# K7410tFFG900Power.net
KiCad netlist of a schematic drawn in Altium Designer
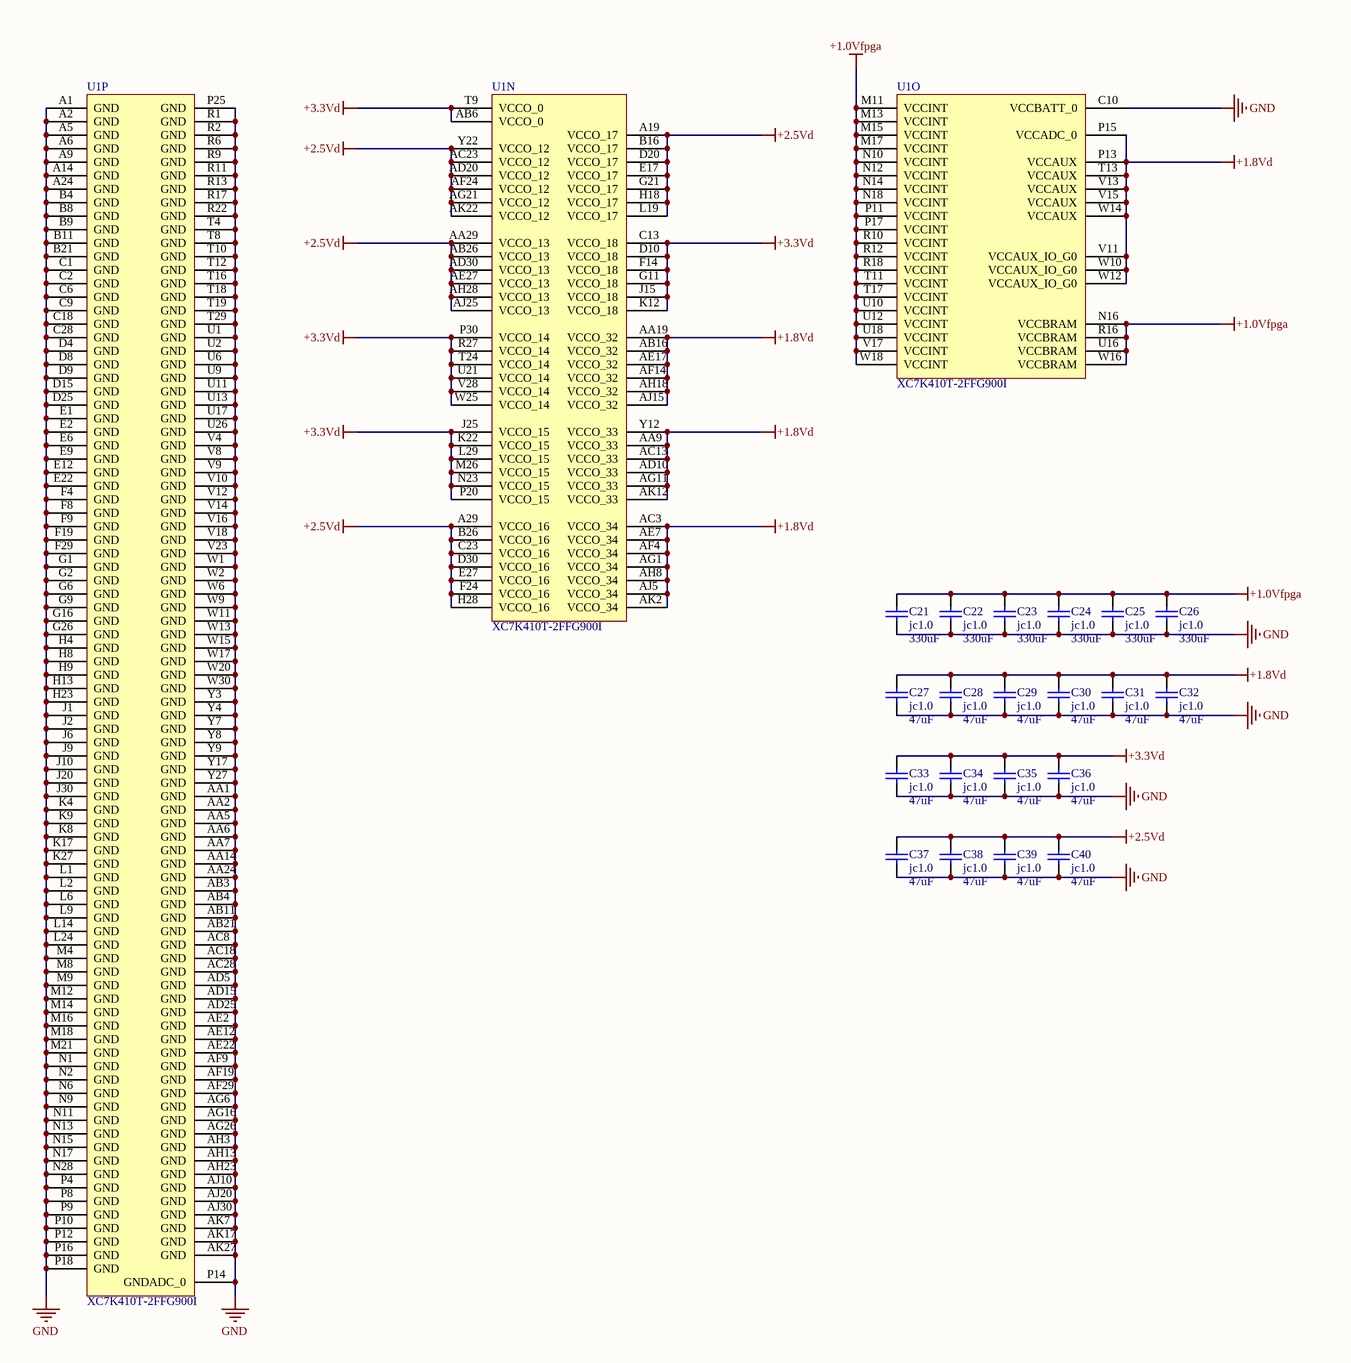
[diagram p0: K7410tFFG900Power.SchDoc]

(export (version "E")
  (design (tool "Eeschema 10.0.6"))
  (components
    (comp (ref "C21")
      (value "jc1.0")
      (footprint "2220")
      (description "Capacitor")
      (fields (field (name "ALTIUM_VALUE") "330uF") (field (name "PUBLISHER") "Altium Limited"))
      (libsource (lib "LIB01DXP2006SchLib") (part "Cap"))
    )
    (comp (ref "C22")
      (value "jc1.0")
      (footprint "2220")
      (description "Capacitor")
      (fields (field (name "ALTIUM_VALUE") "330uF") (field (name "PUBLISHER") "Altium Limited"))
      (libsource (lib "LIB01DXP2006SchLib") (part "Cap"))
    )
    (comp (ref "C23")
      (value "jc1.0")
      (footprint "2220")
      (description "Capacitor")
      (fields (field (name "ALTIUM_VALUE") "330uF") (field (name "PUBLISHER") "Altium Limited"))
      (libsource (lib "LIB01DXP2006SchLib") (part "Cap"))
    )
    (comp (ref "C24")
      (value "jc1.0")
      (footprint "2220")
      (description "Capacitor")
      (fields (field (name "ALTIUM_VALUE") "330uF") (field (name "PUBLISHER") "Altium Limited"))
      (libsource (lib "LIB01DXP2006SchLib") (part "Cap"))
    )
    (comp (ref "C25")
      (value "jc1.0")
      (footprint "2220")
      (description "Capacitor")
      (fields (field (name "ALTIUM_VALUE") "330uF") (field (name "PUBLISHER") "Altium Limited"))
      (libsource (lib "LIB01DXP2006SchLib") (part "Cap"))
    )
    (comp (ref "C26")
      (value "jc1.0")
      (footprint "2220")
      (description "Capacitor")
      (fields (field (name "ALTIUM_VALUE") "330uF") (field (name "PUBLISHER") "Altium Limited"))
      (libsource (lib "LIB01DXP2006SchLib") (part "Cap"))
    )
    (comp (ref "C27")
      (value "jc1.0")
      (footprint "1210")
      (description "Capacitor")
      (fields (field (name "ALTIUM_VALUE") "47uF") (field (name "PUBLISHER") "Altium Limited"))
      (libsource (lib "LIB01DXP2006SchLib") (part "Cap"))
    )
    (comp (ref "C28")
      (value "jc1.0")
      (footprint "1210")
      (description "Capacitor")
      (fields (field (name "ALTIUM_VALUE") "47uF") (field (name "PUBLISHER") "Altium Limited"))
      (libsource (lib "LIB01DXP2006SchLib") (part "Cap"))
    )
    (comp (ref "C29")
      (value "jc1.0")
      (footprint "1210")
      (description "Capacitor")
      (fields (field (name "ALTIUM_VALUE") "47uF") (field (name "PUBLISHER") "Altium Limited"))
      (libsource (lib "LIB01DXP2006SchLib") (part "Cap"))
    )
    (comp (ref "C30")
      (value "jc1.0")
      (footprint "1210")
      (description "Capacitor")
      (fields (field (name "ALTIUM_VALUE") "47uF") (field (name "PUBLISHER") "Altium Limited"))
      (libsource (lib "LIB01DXP2006SchLib") (part "Cap"))
    )
    (comp (ref "C31")
      (value "jc1.0")
      (footprint "1210")
      (description "Capacitor")
      (fields (field (name "ALTIUM_VALUE") "47uF") (field (name "PUBLISHER") "Altium Limited"))
      (libsource (lib "LIB01DXP2006SchLib") (part "Cap"))
    )
    (comp (ref "C32")
      (value "jc1.0")
      (footprint "1210")
      (description "Capacitor")
      (fields (field (name "ALTIUM_VALUE") "47uF") (field (name "PUBLISHER") "Altium Limited"))
      (libsource (lib "LIB01DXP2006SchLib") (part "Cap"))
    )
    (comp (ref "C33")
      (value "jc1.0")
      (footprint "1210")
      (description "Capacitor")
      (fields (field (name "ALTIUM_VALUE") "47uF") (field (name "PUBLISHER") "Altium Limited"))
      (libsource (lib "LIB01DXP2006SchLib") (part "Cap"))
    )
    (comp (ref "C34")
      (value "jc1.0")
      (footprint "1210")
      (description "Capacitor")
      (fields (field (name "ALTIUM_VALUE") "47uF") (field (name "PUBLISHER") "Altium Limited"))
      (libsource (lib "LIB01DXP2006SchLib") (part "Cap"))
    )
    (comp (ref "C35")
      (value "jc1.0")
      (footprint "1210")
      (description "Capacitor")
      (fields (field (name "ALTIUM_VALUE") "47uF") (field (name "PUBLISHER") "Altium Limited"))
      (libsource (lib "LIB01DXP2006SchLib") (part "Cap"))
    )
    (comp (ref "C36")
      (value "jc1.0")
      (footprint "1210")
      (description "Capacitor")
      (fields (field (name "ALTIUM_VALUE") "47uF") (field (name "PUBLISHER") "Altium Limited"))
      (libsource (lib "LIB01DXP2006SchLib") (part "Cap"))
    )
    (comp (ref "C37")
      (value "jc1.0")
      (footprint "1210")
      (description "Capacitor")
      (fields (field (name "ALTIUM_VALUE") "47uF") (field (name "PUBLISHER") "Altium Limited"))
      (libsource (lib "LIB01DXP2006SchLib") (part "Cap"))
    )
    (comp (ref "C38")
      (value "jc1.0")
      (footprint "1210")
      (description "Capacitor")
      (fields (field (name "ALTIUM_VALUE") "47uF") (field (name "PUBLISHER") "Altium Limited"))
      (libsource (lib "LIB01DXP2006SchLib") (part "Cap"))
    )
    (comp (ref "C39")
      (value "jc1.0")
      (footprint "1210")
      (description "Capacitor")
      (fields (field (name "ALTIUM_VALUE") "47uF") (field (name "PUBLISHER") "Altium Limited"))
      (libsource (lib "LIB01DXP2006SchLib") (part "Cap"))
    )
    (comp (ref "C40")
      (value "jc1.0")
      (footprint "1210")
      (description "Capacitor")
      (fields (field (name "ALTIUM_VALUE") "47uF") (field (name "PUBLISHER") "Altium Limited"))
      (libsource (lib "LIB01DXP2006SchLib") (part "Cap"))
    )
    (comp (ref "U1")
      (value "XC7K410T-2FFG900I")
      (footprint "FFG900")
      (description "Kintex-7 FPGA, 500 User I/Os, 16 GTX, 900-Ball BGA, Speed Grade 2, Industrial Grade, Pb-Free")
      (fields (field (name "GENERIC PART NUMBER") "XC7K410T") (field (name "MANUFACTURER") "Xilinx"))
      (libsource (lib "Xilinx Kintex-7") (part "XC7K410T-2FFG900I"))
    )
  )
  (nets
    (net (code "1") (name "+1.0Vfpga") (class "Default")
      (node (ref "C21") (pin "2") (pinfunction "2_2") (pintype "passive"))
      (node (ref "C22") (pin "2") (pinfunction "2_2") (pintype "passive"))
      (node (ref "C23") (pin "2") (pinfunction "2_2") (pintype "passive"))
      (node (ref "C24") (pin "2") (pinfunction "2_2") (pintype "passive"))
      (node (ref "C25") (pin "2") (pinfunction "2_2") (pintype "passive"))
      (node (ref "C26") (pin "2") (pinfunction "2_2") (pintype "passive"))
      (node (ref "U1") (pin "M11") (pinfunction "VCCINT_M11") (pintype "power_in"))
      (node (ref "U1") (pin "M13") (pinfunction "VCCINT_M13") (pintype "power_in"))
      (node (ref "U1") (pin "M15") (pinfunction "VCCINT_M15") (pintype "power_in"))
      (node (ref "U1") (pin "M17") (pinfunction "VCCINT_M17") (pintype "power_in"))
      (node (ref "U1") (pin "N10") (pinfunction "VCCINT_N10") (pintype "power_in"))
      (node (ref "U1") (pin "N12") (pinfunction "VCCINT_N12") (pintype "power_in"))
      (node (ref "U1") (pin "N14") (pinfunction "VCCINT_N14") (pintype "power_in"))
      (node (ref "U1") (pin "N16") (pinfunction "VCCBRAM_N16") (pintype "power_in"))
      (node (ref "U1") (pin "N18") (pinfunction "VCCINT_N18") (pintype "power_in"))
      (node (ref "U1") (pin "P11") (pinfunction "VCCINT_P11") (pintype "power_in"))
      (node (ref "U1") (pin "P17") (pinfunction "VCCINT_P17") (pintype "power_in"))
      (node (ref "U1") (pin "R10") (pinfunction "VCCINT_R10") (pintype "power_in"))
      (node (ref "U1") (pin "R12") (pinfunction "VCCINT_R12") (pintype "power_in"))
      (node (ref "U1") (pin "R16") (pinfunction "VCCBRAM_R16") (pintype "power_in"))
      (node (ref "U1") (pin "R18") (pinfunction "VCCINT_R18") (pintype "power_in"))
      (node (ref "U1") (pin "T11") (pinfunction "VCCINT_T11") (pintype "power_in"))
      (node (ref "U1") (pin "T17") (pinfunction "VCCINT_T17") (pintype "power_in"))
      (node (ref "U1") (pin "U10") (pinfunction "VCCINT_U10") (pintype "power_in"))
      (node (ref "U1") (pin "U12") (pinfunction "VCCINT_U12") (pintype "power_in"))
      (node (ref "U1") (pin "U16") (pinfunction "VCCBRAM_U16") (pintype "power_in"))
      (node (ref "U1") (pin "U18") (pinfunction "VCCINT_U18") (pintype "power_in"))
      (node (ref "U1") (pin "V17") (pinfunction "VCCINT_V17") (pintype "power_in"))
      (node (ref "U1") (pin "W16") (pinfunction "VCCBRAM_W16") (pintype "power_in"))
      (node (ref "U1") (pin "W18") (pinfunction "VCCINT_W18") (pintype "power_in"))
    )
    (net (code "2") (name "+1.8Vd") (class "Default")
      (node (ref "C27") (pin "2") (pinfunction "2_2") (pintype "passive"))
      (node (ref "C28") (pin "2") (pinfunction "2_2") (pintype "passive"))
      (node (ref "C29") (pin "2") (pinfunction "2_2") (pintype "passive"))
      (node (ref "C30") (pin "2") (pinfunction "2_2") (pintype "passive"))
      (node (ref "C31") (pin "2") (pinfunction "2_2") (pintype "passive"))
      (node (ref "C32") (pin "2") (pinfunction "2_2") (pintype "passive"))
      (node (ref "U1") (pin "AA19") (pinfunction "VCCO_32_AA19") (pintype "power_in"))
      (node (ref "U1") (pin "AA9") (pinfunction "VCCO_33_AA9") (pintype "power_in"))
      (node (ref "U1") (pin "AB16") (pinfunction "VCCO_32_AB16") (pintype "power_in"))
      (node (ref "U1") (pin "AC13") (pinfunction "VCCO_33_AC13") (pintype "power_in"))
      (node (ref "U1") (pin "AC3") (pinfunction "VCCO_34_AC3") (pintype "power_in"))
      (node (ref "U1") (pin "AD10") (pinfunction "VCCO_33_AD10") (pintype "power_in"))
      (node (ref "U1") (pin "AE17") (pinfunction "VCCO_32_AE17") (pintype "power_in"))
      (node (ref "U1") (pin "AE7") (pinfunction "VCCO_34_AE7") (pintype "power_in"))
      (node (ref "U1") (pin "AF14") (pinfunction "VCCO_32_AF14") (pintype "power_in"))
      (node (ref "U1") (pin "AF4") (pinfunction "VCCO_34_AF4") (pintype "power_in"))
      (node (ref "U1") (pin "AG1") (pinfunction "VCCO_34_AG1") (pintype "power_in"))
      (node (ref "U1") (pin "AG11") (pinfunction "VCCO_33_AG11") (pintype "power_in"))
      (node (ref "U1") (pin "AH18") (pinfunction "VCCO_32_AH18") (pintype "power_in"))
      (node (ref "U1") (pin "AH8") (pinfunction "VCCO_34_AH8") (pintype "power_in"))
      (node (ref "U1") (pin "AJ15") (pinfunction "VCCO_32_AJ15") (pintype "power_in"))
      (node (ref "U1") (pin "AJ5") (pinfunction "VCCO_34_AJ5") (pintype "power_in"))
      (node (ref "U1") (pin "AK12") (pinfunction "VCCO_33_AK12") (pintype "power_in"))
      (node (ref "U1") (pin "AK2") (pinfunction "VCCO_34_AK2") (pintype "power_in"))
      (node (ref "U1") (pin "P13") (pinfunction "VCCAUX_P13") (pintype "power_in"))
      (node (ref "U1") (pin "P15") (pinfunction "VCCADC_0_P15") (pintype "power_in"))
      (node (ref "U1") (pin "T13") (pinfunction "VCCAUX_T13") (pintype "power_in"))
      (node (ref "U1") (pin "V11") (pinfunction "VCCAUX_IO_G0_V11") (pintype "power_in"))
      (node (ref "U1") (pin "V13") (pinfunction "VCCAUX_V13") (pintype "power_in"))
      (node (ref "U1") (pin "V15") (pinfunction "VCCAUX_V15") (pintype "power_in"))
      (node (ref "U1") (pin "W10") (pinfunction "VCCAUX_IO_G0_W10") (pintype "power_in"))
      (node (ref "U1") (pin "W12") (pinfunction "VCCAUX_IO_G0_W12") (pintype "power_in"))
      (node (ref "U1") (pin "W14") (pinfunction "VCCAUX_W14") (pintype "power_in"))
      (node (ref "U1") (pin "Y12") (pinfunction "VCCO_33_Y12") (pintype "power_in"))
    )
    (net (code "3") (name "+2.5Vd") (class "Default")
      (node (ref "C37") (pin "2") (pinfunction "2_2") (pintype "passive"))
      (node (ref "C38") (pin "2") (pinfunction "2_2") (pintype "passive"))
      (node (ref "C39") (pin "2") (pinfunction "2_2") (pintype "passive"))
      (node (ref "C40") (pin "2") (pinfunction "2_2") (pintype "passive"))
      (node (ref "U1") (pin "A19") (pinfunction "VCCO_17_A19") (pintype "power_in"))
      (node (ref "U1") (pin "A29") (pinfunction "VCCO_16_A29") (pintype "power_in"))
      (node (ref "U1") (pin "AA29") (pinfunction "VCCO_13_AA29") (pintype "power_in"))
      (node (ref "U1") (pin "AB26") (pinfunction "VCCO_13_AB26") (pintype "power_in"))
      (node (ref "U1") (pin "AC23") (pinfunction "VCCO_12_AC23") (pintype "power_in"))
      (node (ref "U1") (pin "AD20") (pinfunction "VCCO_12_AD20") (pintype "power_in"))
      (node (ref "U1") (pin "AD30") (pinfunction "VCCO_13_AD30") (pintype "power_in"))
      (node (ref "U1") (pin "AE27") (pinfunction "VCCO_13_AE27") (pintype "power_in"))
      (node (ref "U1") (pin "AF24") (pinfunction "VCCO_12_AF24") (pintype "power_in"))
      (node (ref "U1") (pin "AG21") (pinfunction "VCCO_12_AG21") (pintype "power_in"))
      (node (ref "U1") (pin "AH28") (pinfunction "VCCO_13_AH28") (pintype "power_in"))
      (node (ref "U1") (pin "AJ25") (pinfunction "VCCO_13_AJ25") (pintype "power_in"))
      (node (ref "U1") (pin "AK22") (pinfunction "VCCO_12_AK22") (pintype "power_in"))
      (node (ref "U1") (pin "B16") (pinfunction "VCCO_17_B16") (pintype "power_in"))
      (node (ref "U1") (pin "B26") (pinfunction "VCCO_16_B26") (pintype "power_in"))
      (node (ref "U1") (pin "C23") (pinfunction "VCCO_16_C23") (pintype "power_in"))
      (node (ref "U1") (pin "D20") (pinfunction "VCCO_17_D20") (pintype "power_in"))
      (node (ref "U1") (pin "D30") (pinfunction "VCCO_16_D30") (pintype "power_in"))
      (node (ref "U1") (pin "E17") (pinfunction "VCCO_17_E17") (pintype "power_in"))
      (node (ref "U1") (pin "E27") (pinfunction "VCCO_16_E27") (pintype "power_in"))
      (node (ref "U1") (pin "F24") (pinfunction "VCCO_16_F24") (pintype "power_in"))
      (node (ref "U1") (pin "G21") (pinfunction "VCCO_17_G21") (pintype "power_in"))
      (node (ref "U1") (pin "H18") (pinfunction "VCCO_17_H18") (pintype "power_in"))
      (node (ref "U1") (pin "H28") (pinfunction "VCCO_16_H28") (pintype "power_in"))
      (node (ref "U1") (pin "L19") (pinfunction "VCCO_17_L19") (pintype "power_in"))
      (node (ref "U1") (pin "Y22") (pinfunction "VCCO_12_Y22") (pintype "power_in"))
    )
    (net (code "4") (name "+3.3Vd") (class "Default")
      (node (ref "C33") (pin "2") (pinfunction "2_2") (pintype "passive"))
      (node (ref "C34") (pin "2") (pinfunction "2_2") (pintype "passive"))
      (node (ref "C35") (pin "2") (pinfunction "2_2") (pintype "passive"))
      (node (ref "C36") (pin "2") (pinfunction "2_2") (pintype "passive"))
      (node (ref "U1") (pin "AB6") (pinfunction "VCCO_0_AB6") (pintype "power_in"))
      (node (ref "U1") (pin "C13") (pinfunction "VCCO_18_C13") (pintype "power_in"))
      (node (ref "U1") (pin "D10") (pinfunction "VCCO_18_D10") (pintype "power_in"))
      (node (ref "U1") (pin "F14") (pinfunction "VCCO_18_F14") (pintype "power_in"))
      (node (ref "U1") (pin "G11") (pinfunction "VCCO_18_G11") (pintype "power_in"))
      (node (ref "U1") (pin "J15") (pinfunction "VCCO_18_J15") (pintype "power_in"))
      (node (ref "U1") (pin "J25") (pinfunction "VCCO_15_J25") (pintype "power_in"))
      (node (ref "U1") (pin "K12") (pinfunction "VCCO_18_K12") (pintype "power_in"))
      (node (ref "U1") (pin "K22") (pinfunction "VCCO_15_K22") (pintype "power_in"))
      (node (ref "U1") (pin "L29") (pinfunction "VCCO_15_L29") (pintype "power_in"))
      (node (ref "U1") (pin "M26") (pinfunction "VCCO_15_M26") (pintype "power_in"))
      (node (ref "U1") (pin "N23") (pinfunction "VCCO_15_N23") (pintype "power_in"))
      (node (ref "U1") (pin "P20") (pinfunction "VCCO_15_P20") (pintype "power_in"))
      (node (ref "U1") (pin "P30") (pinfunction "VCCO_14_P30") (pintype "power_in"))
      (node (ref "U1") (pin "R27") (pinfunction "VCCO_14_R27") (pintype "power_in"))
      (node (ref "U1") (pin "T24") (pinfunction "VCCO_14_T24") (pintype "power_in"))
      (node (ref "U1") (pin "T9") (pinfunction "VCCO_0_T9") (pintype "power_in"))
      (node (ref "U1") (pin "U21") (pinfunction "VCCO_14_U21") (pintype "power_in"))
      (node (ref "U1") (pin "V28") (pinfunction "VCCO_14_V28") (pintype "power_in"))
      (node (ref "U1") (pin "W25") (pinfunction "VCCO_14_W25") (pintype "power_in"))
    )
    (net (code "5") (name "GND") (class "Default")
      (node (ref "C21") (pin "1") (pinfunction "1_1") (pintype "passive"))
      (node (ref "C22") (pin "1") (pinfunction "1_1") (pintype "passive"))
      (node (ref "C23") (pin "1") (pinfunction "1_1") (pintype "passive"))
      (node (ref "C24") (pin "1") (pinfunction "1_1") (pintype "passive"))
      (node (ref "C25") (pin "1") (pinfunction "1_1") (pintype "passive"))
      (node (ref "C26") (pin "1") (pinfunction "1_1") (pintype "passive"))
      (node (ref "C27") (pin "1") (pinfunction "1_1") (pintype "passive"))
      (node (ref "C28") (pin "1") (pinfunction "1_1") (pintype "passive"))
      (node (ref "C29") (pin "1") (pinfunction "1_1") (pintype "passive"))
      (node (ref "C30") (pin "1") (pinfunction "1_1") (pintype "passive"))
      (node (ref "C31") (pin "1") (pinfunction "1_1") (pintype "passive"))
      (node (ref "C32") (pin "1") (pinfunction "1_1") (pintype "passive"))
      (node (ref "C33") (pin "1") (pinfunction "1_1") (pintype "passive"))
      (node (ref "C34") (pin "1") (pinfunction "1_1") (pintype "passive"))
      (node (ref "C35") (pin "1") (pinfunction "1_1") (pintype "passive"))
      (node (ref "C36") (pin "1") (pinfunction "1_1") (pintype "passive"))
      (node (ref "C37") (pin "1") (pinfunction "1_1") (pintype "passive"))
      (node (ref "C38") (pin "1") (pinfunction "1_1") (pintype "passive"))
      (node (ref "C39") (pin "1") (pinfunction "1_1") (pintype "passive"))
      (node (ref "C40") (pin "1") (pinfunction "1_1") (pintype "passive"))
      (node (ref "U1") (pin "A1") (pinfunction "GND_A1") (pintype "power_in"))
      (node (ref "U1") (pin "A14") (pinfunction "GND_A14") (pintype "power_in"))
      (node (ref "U1") (pin "A2") (pinfunction "GND_A2") (pintype "power_in"))
      (node (ref "U1") (pin "A24") (pinfunction "GND_A24") (pintype "power_in"))
      (node (ref "U1") (pin "A5") (pinfunction "GND_A5") (pintype "power_in"))
      (node (ref "U1") (pin "A6") (pinfunction "GND_A6") (pintype "power_in"))
      (node (ref "U1") (pin "A9") (pinfunction "GND_A9") (pintype "power_in"))
      (node (ref "U1") (pin "AA1") (pinfunction "GND_AA1") (pintype "power_in"))
      (node (ref "U1") (pin "AA14") (pinfunction "GND_AA14") (pintype "power_in"))
      (node (ref "U1") (pin "AA2") (pinfunction "GND_AA2") (pintype "power_in"))
      (node (ref "U1") (pin "AA24") (pinfunction "GND_AA24") (pintype "power_in"))
      (node (ref "U1") (pin "AA5") (pinfunction "GND_AA5") (pintype "power_in"))
      (node (ref "U1") (pin "AA6") (pinfunction "GND_AA6") (pintype "power_in"))
      (node (ref "U1") (pin "AA7") (pinfunction "GND_AA7") (pintype "power_in"))
      (node (ref "U1") (pin "AB11") (pinfunction "GND_AB11") (pintype "power_in"))
      (node (ref "U1") (pin "AB21") (pinfunction "GND_AB21") (pintype "power_in"))
      (node (ref "U1") (pin "AB3") (pinfunction "GND_AB3") (pintype "power_in"))
      (node (ref "U1") (pin "AB4") (pinfunction "GND_AB4") (pintype "power_in"))
      (node (ref "U1") (pin "AC18") (pinfunction "GND_AC18") (pintype "power_in"))
      (node (ref "U1") (pin "AC28") (pinfunction "GND_AC28") (pintype "power_in"))
      (node (ref "U1") (pin "AC8") (pinfunction "GND_AC8") (pintype "power_in"))
      (node (ref "U1") (pin "AD15") (pinfunction "GND_AD15") (pintype "power_in"))
      (node (ref "U1") (pin "AD25") (pinfunction "GND_AD25") (pintype "power_in"))
      (node (ref "U1") (pin "AD5") (pinfunction "GND_AD5") (pintype "power_in"))
      (node (ref "U1") (pin "AE12") (pinfunction "GND_AE12") (pintype "power_in"))
      (node (ref "U1") (pin "AE2") (pinfunction "GND_AE2") (pintype "power_in"))
      (node (ref "U1") (pin "AE22") (pinfunction "GND_AE22") (pintype "power_in"))
      (node (ref "U1") (pin "AF19") (pinfunction "GND_AF19") (pintype "power_in"))
      (node (ref "U1") (pin "AF29") (pinfunction "GND_AF29") (pintype "power_in"))
      (node (ref "U1") (pin "AF9") (pinfunction "GND_AF9") (pintype "power_in"))
      (node (ref "U1") (pin "AG16") (pinfunction "GND_AG16") (pintype "power_in"))
      (node (ref "U1") (pin "AG26") (pinfunction "GND_AG26") (pintype "power_in"))
      (node (ref "U1") (pin "AG6") (pinfunction "GND_AG6") (pintype "power_in"))
      (node (ref "U1") (pin "AH13") (pinfunction "GND_AH13") (pintype "power_in"))
      (node (ref "U1") (pin "AH23") (pinfunction "GND_AH23") (pintype "power_in"))
      (node (ref "U1") (pin "AH3") (pinfunction "GND_AH3") (pintype "power_in"))
      (node (ref "U1") (pin "AJ10") (pinfunction "GND_AJ10") (pintype "power_in"))
      (node (ref "U1") (pin "AJ20") (pinfunction "GND_AJ20") (pintype "power_in"))
      (node (ref "U1") (pin "AJ30") (pinfunction "GND_AJ30") (pintype "power_in"))
      (node (ref "U1") (pin "AK17") (pinfunction "GND_AK17") (pintype "power_in"))
      (node (ref "U1") (pin "AK27") (pinfunction "GND_AK27") (pintype "power_in"))
      (node (ref "U1") (pin "AK7") (pinfunction "GND_AK7") (pintype "power_in"))
      (node (ref "U1") (pin "B11") (pinfunction "GND_B11") (pintype "power_in"))
      (node (ref "U1") (pin "B21") (pinfunction "GND_B21") (pintype "power_in"))
      (node (ref "U1") (pin "B4") (pinfunction "GND_B4") (pintype "power_in"))
      (node (ref "U1") (pin "B8") (pinfunction "GND_B8") (pintype "power_in"))
      (node (ref "U1") (pin "B9") (pinfunction "GND_B9") (pintype "power_in"))
      (node (ref "U1") (pin "C1") (pinfunction "GND_C1") (pintype "power_in"))
      (node (ref "U1") (pin "C10") (pinfunction "VCCBATT_0_C10") (pintype "power_in"))
      (node (ref "U1") (pin "C18") (pinfunction "GND_C18") (pintype "power_in"))
      (node (ref "U1") (pin "C2") (pinfunction "GND_C2") (pintype "power_in"))
      (node (ref "U1") (pin "C28") (pinfunction "GND_C28") (pintype "power_in"))
      (node (ref "U1") (pin "C6") (pinfunction "GND_C6") (pintype "power_in"))
      (node (ref "U1") (pin "C9") (pinfunction "GND_C9") (pintype "power_in"))
      (node (ref "U1") (pin "D15") (pinfunction "GND_D15") (pintype "power_in"))
      (node (ref "U1") (pin "D25") (pinfunction "GND_D25") (pintype "power_in"))
      (node (ref "U1") (pin "D4") (pinfunction "GND_D4") (pintype "power_in"))
      (node (ref "U1") (pin "D8") (pinfunction "GND_D8") (pintype "power_in"))
      (node (ref "U1") (pin "D9") (pinfunction "GND_D9") (pintype "power_in"))
      (node (ref "U1") (pin "E1") (pinfunction "GND_E1") (pintype "power_in"))
      (node (ref "U1") (pin "E12") (pinfunction "GND_E12") (pintype "power_in"))
      (node (ref "U1") (pin "E2") (pinfunction "GND_E2") (pintype "power_in"))
      (node (ref "U1") (pin "E22") (pinfunction "GND_E22") (pintype "power_in"))
      (node (ref "U1") (pin "E6") (pinfunction "GND_E6") (pintype "power_in"))
      (node (ref "U1") (pin "E9") (pinfunction "GND_E9") (pintype "power_in"))
      (node (ref "U1") (pin "F19") (pinfunction "GND_F19") (pintype "power_in"))
      (node (ref "U1") (pin "F29") (pinfunction "GND_F29") (pintype "power_in"))
      (node (ref "U1") (pin "F4") (pinfunction "GND_F4") (pintype "power_in"))
      (node (ref "U1") (pin "F8") (pinfunction "GND_F8") (pintype "power_in"))
      (node (ref "U1") (pin "F9") (pinfunction "GND_F9") (pintype "power_in"))
      (node (ref "U1") (pin "G1") (pinfunction "GND_G1") (pintype "power_in"))
      (node (ref "U1") (pin "G16") (pinfunction "GND_G16") (pintype "power_in"))
      (node (ref "U1") (pin "G2") (pinfunction "GND_G2") (pintype "power_in"))
      (node (ref "U1") (pin "G26") (pinfunction "GND_G26") (pintype "power_in"))
      (node (ref "U1") (pin "G6") (pinfunction "GND_G6") (pintype "power_in"))
      (node (ref "U1") (pin "G9") (pinfunction "GND_G9") (pintype "power_in"))
      (node (ref "U1") (pin "H13") (pinfunction "GND_H13") (pintype "power_in"))
      (node (ref "U1") (pin "H23") (pinfunction "GND_H23") (pintype "power_in"))
      (node (ref "U1") (pin "H4") (pinfunction "GND_H4") (pintype "power_in"))
      (node (ref "U1") (pin "H8") (pinfunction "GND_H8") (pintype "power_in"))
      (node (ref "U1") (pin "H9") (pinfunction "GND_H9") (pintype "power_in"))
      (node (ref "U1") (pin "J1") (pinfunction "GND_J1") (pintype "power_in"))
      (node (ref "U1") (pin "J10") (pinfunction "GND_J10") (pintype "power_in"))
      (node (ref "U1") (pin "J2") (pinfunction "GND_J2") (pintype "power_in"))
      (node (ref "U1") (pin "J20") (pinfunction "GND_J20") (pintype "power_in"))
      (node (ref "U1") (pin "J30") (pinfunction "GND_J30") (pintype "power_in"))
      (node (ref "U1") (pin "J6") (pinfunction "GND_J6") (pintype "power_in"))
      (node (ref "U1") (pin "J9") (pinfunction "GND_J9") (pintype "power_in"))
      (node (ref "U1") (pin "K17") (pinfunction "GND_K17") (pintype "power_in"))
      (node (ref "U1") (pin "K27") (pinfunction "GND_K27") (pintype "power_in"))
      (node (ref "U1") (pin "K4") (pinfunction "GND_K4") (pintype "power_in"))
      (node (ref "U1") (pin "K8") (pinfunction "GND_K8") (pintype "power_in"))
      (node (ref "U1") (pin "K9") (pinfunction "GND_K9") (pintype "power_in"))
      (node (ref "U1") (pin "L1") (pinfunction "GND_L1") (pintype "power_in"))
      (node (ref "U1") (pin "L14") (pinfunction "GND_L14") (pintype "power_in"))
      (node (ref "U1") (pin "L2") (pinfunction "GND_L2") (pintype "power_in"))
      (node (ref "U1") (pin "L24") (pinfunction "GND_L24") (pintype "power_in"))
      (node (ref "U1") (pin "L6") (pinfunction "GND_L6") (pintype "power_in"))
      (node (ref "U1") (pin "L9") (pinfunction "GND_L9") (pintype "power_in"))
      (node (ref "U1") (pin "M12") (pinfunction "GND_M12") (pintype "power_in"))
      (node (ref "U1") (pin "M14") (pinfunction "GND_M14") (pintype "power_in"))
      (node (ref "U1") (pin "M16") (pinfunction "GND_M16") (pintype "power_in"))
      (node (ref "U1") (pin "M18") (pinfunction "GND_M18") (pintype "power_in"))
      (node (ref "U1") (pin "M21") (pinfunction "GND_M21") (pintype "power_in"))
      (node (ref "U1") (pin "M4") (pinfunction "GND_M4") (pintype "power_in"))
      (node (ref "U1") (pin "M8") (pinfunction "GND_M8") (pintype "power_in"))
      (node (ref "U1") (pin "M9") (pinfunction "GND_M9") (pintype "power_in"))
      (node (ref "U1") (pin "N1") (pinfunction "GND_N1") (pintype "power_in"))
      (node (ref "U1") (pin "N11") (pinfunction "GND_N11") (pintype "power_in"))
      (node (ref "U1") (pin "N13") (pinfunction "GND_N13") (pintype "power_in"))
      (node (ref "U1") (pin "N15") (pinfunction "GND_N15") (pintype "power_in"))
      (node (ref "U1") (pin "N17") (pinfunction "GND_N17") (pintype "power_in"))
      (node (ref "U1") (pin "N2") (pinfunction "GND_N2") (pintype "power_in"))
      (node (ref "U1") (pin "N28") (pinfunction "GND_N28") (pintype "power_in"))
      (node (ref "U1") (pin "N6") (pinfunction "GND_N6") (pintype "power_in"))
      (node (ref "U1") (pin "N9") (pinfunction "GND_N9") (pintype "power_in"))
      (node (ref "U1") (pin "P10") (pinfunction "GND_P10") (pintype "power_in"))
      (node (ref "U1") (pin "P12") (pinfunction "GND_P12") (pintype "power_in"))
      (node (ref "U1") (pin "P14") (pinfunction "GNDADC_0_P14") (pintype "power_in"))
      (node (ref "U1") (pin "P16") (pinfunction "GND_P16") (pintype "power_in"))
      (node (ref "U1") (pin "P18") (pinfunction "GND_P18") (pintype "power_in"))
      (node (ref "U1") (pin "P25") (pinfunction "GND_P25") (pintype "power_in"))
      (node (ref "U1") (pin "P4") (pinfunction "GND_P4") (pintype "power_in"))
      (node (ref "U1") (pin "P8") (pinfunction "GND_P8") (pintype "power_in"))
      (node (ref "U1") (pin "P9") (pinfunction "GND_P9") (pintype "power_in"))
      (node (ref "U1") (pin "R1") (pinfunction "GND_R1") (pintype "power_in"))
      (node (ref "U1") (pin "R11") (pinfunction "GND_R11") (pintype "power_in"))
      (node (ref "U1") (pin "R13") (pinfunction "GND_R13") (pintype "power_in"))
      (node (ref "U1") (pin "R17") (pinfunction "GND_R17") (pintype "power_in"))
      (node (ref "U1") (pin "R2") (pinfunction "GND_R2") (pintype "power_in"))
      (node (ref "U1") (pin "R22") (pinfunction "GND_R22") (pintype "power_in"))
      (node (ref "U1") (pin "R6") (pinfunction "GND_R6") (pintype "power_in"))
      (node (ref "U1") (pin "R9") (pinfunction "GND_R9") (pintype "power_in"))
      (node (ref "U1") (pin "T10") (pinfunction "GND_T10") (pintype "power_in"))
      (node (ref "U1") (pin "T12") (pinfunction "GND_T12") (pintype "power_in"))
      (node (ref "U1") (pin "T16") (pinfunction "GND_T16") (pintype "power_in"))
      (node (ref "U1") (pin "T18") (pinfunction "GND_T18") (pintype "power_in"))
      (node (ref "U1") (pin "T19") (pinfunction "GND_T19") (pintype "power_in"))
      (node (ref "U1") (pin "T29") (pinfunction "GND_T29") (pintype "power_in"))
      (node (ref "U1") (pin "T4") (pinfunction "GND_T4") (pintype "power_in"))
      (node (ref "U1") (pin "T8") (pinfunction "GND_T8") (pintype "power_in"))
      (node (ref "U1") (pin "U1") (pinfunction "GND_U1") (pintype "power_in"))
      (node (ref "U1") (pin "U11") (pinfunction "GND_U11") (pintype "power_in"))
      (node (ref "U1") (pin "U13") (pinfunction "GND_U13") (pintype "power_in"))
      (node (ref "U1") (pin "U17") (pinfunction "GND_U17") (pintype "power_in"))
      (node (ref "U1") (pin "U2") (pinfunction "GND_U2") (pintype "power_in"))
      (node (ref "U1") (pin "U26") (pinfunction "GND_U26") (pintype "power_in"))
      (node (ref "U1") (pin "U6") (pinfunction "GND_U6") (pintype "power_in"))
      (node (ref "U1") (pin "U9") (pinfunction "GND_U9") (pintype "power_in"))
      (node (ref "U1") (pin "V10") (pinfunction "GND_V10") (pintype "power_in"))
      (node (ref "U1") (pin "V12") (pinfunction "GND_V12") (pintype "power_in"))
      (node (ref "U1") (pin "V14") (pinfunction "GND_V14") (pintype "power_in"))
      (node (ref "U1") (pin "V16") (pinfunction "GND_V16") (pintype "power_in"))
      (node (ref "U1") (pin "V18") (pinfunction "GND_V18") (pintype "power_in"))
      (node (ref "U1") (pin "V23") (pinfunction "GND_V23") (pintype "power_in"))
      (node (ref "U1") (pin "V4") (pinfunction "GND_V4") (pintype "power_in"))
      (node (ref "U1") (pin "V8") (pinfunction "GND_V8") (pintype "power_in"))
      (node (ref "U1") (pin "V9") (pinfunction "GND_V9") (pintype "power_in"))
      (node (ref "U1") (pin "W1") (pinfunction "GND_W1") (pintype "power_in"))
      (node (ref "U1") (pin "W11") (pinfunction "GND_W11") (pintype "power_in"))
      (node (ref "U1") (pin "W13") (pinfunction "GND_W13") (pintype "power_in"))
      (node (ref "U1") (pin "W15") (pinfunction "GND_W15") (pintype "power_in"))
      (node (ref "U1") (pin "W17") (pinfunction "GND_W17") (pintype "power_in"))
      (node (ref "U1") (pin "W2") (pinfunction "GND_W2") (pintype "power_in"))
      (node (ref "U1") (pin "W20") (pinfunction "GND_W20") (pintype "power_in"))
      (node (ref "U1") (pin "W30") (pinfunction "GND_W30") (pintype "power_in"))
      (node (ref "U1") (pin "W6") (pinfunction "GND_W6") (pintype "power_in"))
      (node (ref "U1") (pin "W9") (pinfunction "GND_W9") (pintype "power_in"))
      (node (ref "U1") (pin "Y17") (pinfunction "GND_Y17") (pintype "power_in"))
      (node (ref "U1") (pin "Y27") (pinfunction "GND_Y27") (pintype "power_in"))
      (node (ref "U1") (pin "Y3") (pinfunction "GND_Y3") (pintype "power_in"))
      (node (ref "U1") (pin "Y4") (pinfunction "GND_Y4") (pintype "power_in"))
      (node (ref "U1") (pin "Y7") (pinfunction "GND_Y7") (pintype "power_in"))
      (node (ref "U1") (pin "Y8") (pinfunction "GND_Y8") (pintype "power_in"))
      (node (ref "U1") (pin "Y9") (pinfunction "GND_Y9") (pintype "power_in"))
    )
  )
)
